# PaxInstruments-T100.net
KiCad netlist of a schematic drawn in EAGLE
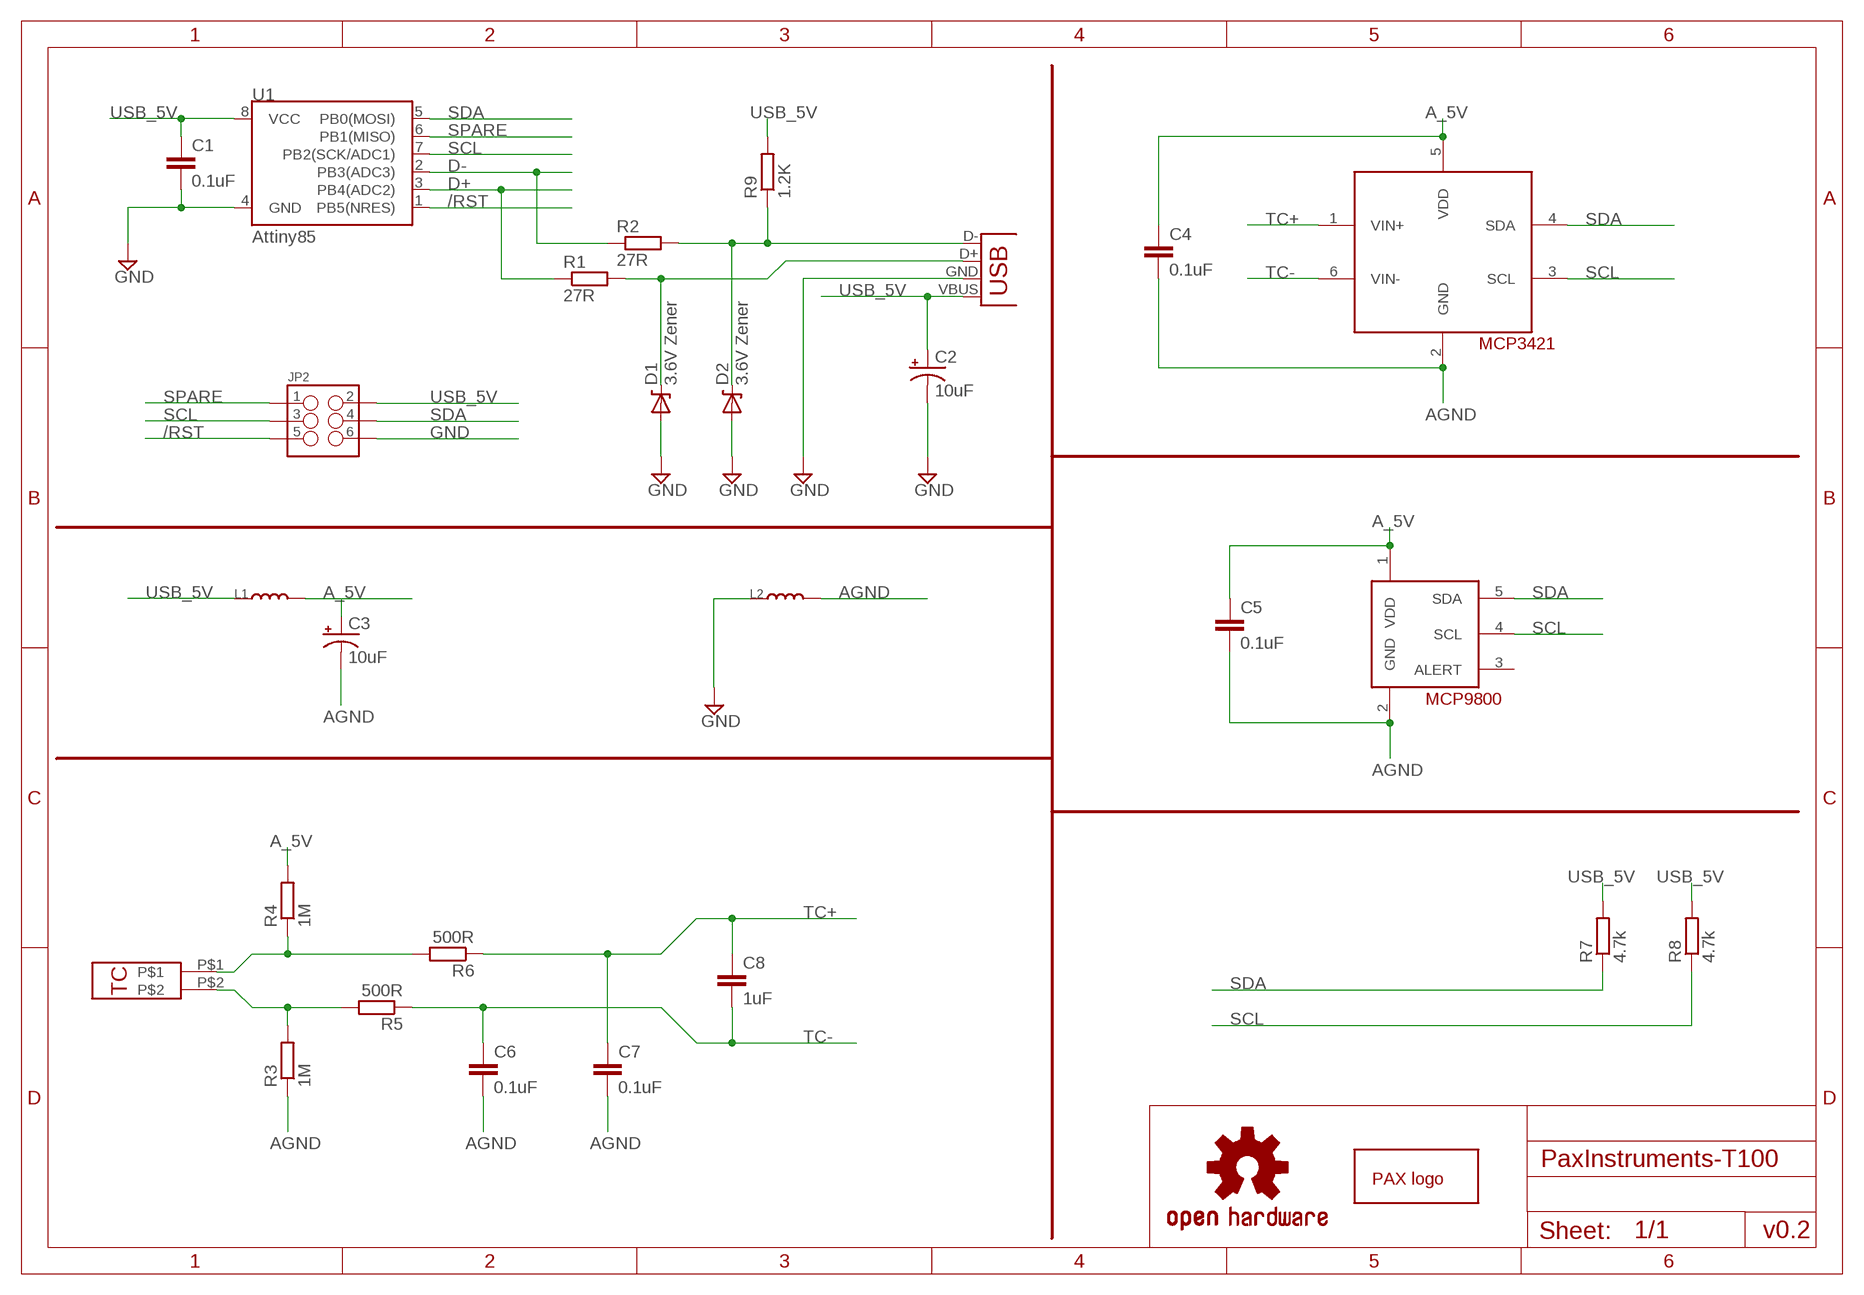
[diagram p0: schematic, sheet 1]

(export (version "E")
  (design (tool "Eeschema 10.0.6"))
  (components
    (comp (ref "C1")
      (value "0.1uF")
      (footprint "eagle-import:C0603")
      (libsource (lib "eagle-import") (part "C-EUC0603"))
    )
    (comp (ref "C2")
      (value "10uF")
      (footprint "eagle-import:EIA3216")
      (libsource (lib "eagle-import") (part "10UF-TANT"))
    )
    (comp (ref "C3")
      (value "10uF")
      (footprint "eagle-import:EIA3216")
      (libsource (lib "eagle-import") (part "10UF-TANT"))
    )
    (comp (ref "C4")
      (value "0.1uF")
      (footprint "eagle-import:C0603")
      (libsource (lib "eagle-import") (part "C-EUC0603"))
    )
    (comp (ref "C5")
      (value "0.1uF")
      (footprint "eagle-import:C0603")
      (libsource (lib "eagle-import") (part "C-EUC0603"))
    )
    (comp (ref "C6")
      (value "0.1uF")
      (footprint "eagle-import:C0603")
      (libsource (lib "eagle-import") (part "C-EUC0603"))
    )
    (comp (ref "C7")
      (value "0.1uF")
      (footprint "eagle-import:C0603")
      (libsource (lib "eagle-import") (part "C-EUC0603"))
    )
    (comp (ref "C8")
      (value "1uF")
      (footprint "eagle-import:C0603")
      (libsource (lib "eagle-import") (part "C-EUC0603"))
    )
    (comp (ref "D1")
      (value "3.6V Zener")
      (footprint "eagle-import:SOD-323")
      (libsource (lib "eagle-import") (part "DIODE-ZENER-BZT52"))
    )
    (comp (ref "D2")
      (value "3.6V Zener")
      (footprint "eagle-import:SOD-323")
      (libsource (lib "eagle-import") (part "DIODE-ZENER-BZT52"))
    )
    (comp (ref "JP1")
      (value "USB-A-H")
      (footprint "eagle-import:USB-A-H")
      (libsource (lib "eagle-import") (part "USB-A-H"))
    )
    (comp (ref "JP2")
      (value "M03X2SMT")
      (footprint "eagle-import:2X3_SMT_POSTS")
      (libsource (lib "eagle-import") (part "M03X2SMT"))
    )
    (comp (ref "L1")
      (value "L-0603")
      (footprint "eagle-import:L0603")
      (libsource (lib "eagle-import") (part "L-0603"))
    )
    (comp (ref "L2")
      (value "L-0603")
      (footprint "eagle-import:L0603")
      (libsource (lib "eagle-import") (part "L-0603"))
    )
    (comp (ref "LOGO1")
      (value "OSHW-LOGOS")
      (footprint "eagle-import:OSHW-LOGO-S")
      (libsource (lib "eagle-import") (part "OSHW-LOGOS"))
    )
    (comp (ref "R1")
      (value "27R")
      (footprint "eagle-import:R0603")
      (libsource (lib "eagle-import") (part "R-EU_R0603"))
    )
    (comp (ref "R2")
      (value "27R")
      (footprint "eagle-import:R0603")
      (libsource (lib "eagle-import") (part "R-EU_R0603"))
    )
    (comp (ref "R3")
      (value "1M")
      (footprint "eagle-import:R0603")
      (libsource (lib "eagle-import") (part "R-EU_R0603"))
    )
    (comp (ref "R4")
      (value "1M")
      (footprint "eagle-import:R0603")
      (libsource (lib "eagle-import") (part "R-EU_R0603"))
    )
    (comp (ref "R5")
      (value "500R")
      (footprint "eagle-import:R0603")
      (libsource (lib "eagle-import") (part "R-EU_R0603"))
    )
    (comp (ref "R6")
      (value "500R")
      (footprint "eagle-import:R0603")
      (libsource (lib "eagle-import") (part "R-EU_R0603"))
    )
    (comp (ref "R7")
      (value "4.7k")
      (footprint "eagle-import:R0603")
      (libsource (lib "eagle-import") (part "R-EU_R0603"))
    )
    (comp (ref "R8")
      (value "4.7k")
      (footprint "eagle-import:R0603")
      (libsource (lib "eagle-import") (part "R-EU_R0603"))
    )
    (comp (ref "R9")
      (value "1.2K")
      (footprint "eagle-import:R0603")
      (libsource (lib "eagle-import") (part "R-EU_R0603"))
    )
    (comp (ref "U$1")
      (value "PAX-LOGO")
      (footprint "eagle-import:PAX-LOGO")
      (libsource (lib "eagle-import") (part "PAX-LOGO"))
    )
    (comp (ref "U$2")
      (value "CHARLESPAX_TC-MINI-CONNECTOR")
      (footprint "eagle-import:CHARLESPAX_TC-MINI-CONNECTOR")
      (libsource (lib "eagle-import") (part "CHARLESPAX_TC-MINI-CONNECTOR"))
    )
    (comp (ref "U$3")
      (value "MCP3421")
      (footprint "eagle-import:SOT23-6")
      (libsource (lib "eagle-import") (part "MCP3421"))
    )
    (comp (ref "U$4")
      (value "MCP9800")
      (footprint "eagle-import:SOT23-5")
      (libsource (lib "eagle-import") (part "MCP9800"))
    )
    (comp (ref "U1")
      (value "Attiny85")
      (footprint "eagle-import:SO08-EIAJ")
      (libsource (lib "eagle-import") (part "ATTINY45TINY45-20-SMT"))
    )
  )
  (nets
    (net (code "1") (name "/AGND") (class "Default")
      (node (ref "C3") (pin "C") (pinfunction "-_C") (pintype "passive"))
      (node (ref "C4") (pin "2") (pinfunction "2_2") (pintype "passive"))
      (node (ref "C5") (pin "2") (pinfunction "2_2") (pintype "passive"))
      (node (ref "C6") (pin "2") (pinfunction "2_2") (pintype "passive"))
      (node (ref "C7") (pin "2") (pinfunction "2_2") (pintype "passive"))
      (node (ref "L2") (pin "2") (pinfunction "2_2") (pintype "passive"))
      (node (ref "R3") (pin "1") (pinfunction "1_1") (pintype "passive"))
      (node (ref "U$3") (pin "2") (pinfunction "GND_2") (pintype "bidirectional"))
      (node (ref "U$4") (pin "2") (pinfunction "GND_2") (pintype "bidirectional"))
    )
    (net (code "2") (name "/A_5V") (class "Default")
      (node (ref "C3") (pin "A") (pinfunction "+_A") (pintype "passive"))
      (node (ref "C4") (pin "1") (pinfunction "1_1") (pintype "passive"))
      (node (ref "C5") (pin "1") (pinfunction "1_1") (pintype "passive"))
      (node (ref "L1") (pin "2") (pinfunction "2_2") (pintype "passive"))
      (node (ref "R4") (pin "2") (pinfunction "2_2") (pintype "passive"))
      (node (ref "U$3") (pin "5") (pinfunction "VDD_5") (pintype "bidirectional"))
      (node (ref "U$4") (pin "1") (pinfunction "VDD_1") (pintype "bidirectional"))
    )
    (net (code "3") (name "/D+") (class "Default")
      (node (ref "R1") (pin "1") (pinfunction "1_1") (pintype "passive"))
      (node (ref "U1") (pin "3") (pinfunction "PB4(ADC2)_3") (pintype "bidirectional"))
    )
    (net (code "4") (name "/D-") (class "Default")
      (node (ref "R2") (pin "1") (pinfunction "1_1") (pintype "passive"))
      (node (ref "U1") (pin "2") (pinfunction "PB3(ADC3)_2") (pintype "bidirectional"))
    )
    (net (code "5") (name "/SCL") (class "Default")
      (node (ref "JP2") (pin "3") (pinfunction "3_3") (pintype "bidirectional"))
      (node (ref "R8") (pin "1") (pinfunction "1_1") (pintype "passive"))
      (node (ref "U$3") (pin "3") (pinfunction "SCL_3") (pintype "bidirectional"))
      (node (ref "U$4") (pin "4") (pinfunction "SCL_4") (pintype "bidirectional"))
      (node (ref "U1") (pin "7") (pinfunction "PB2(SCK/ADC1)_7") (pintype "bidirectional"))
    )
    (net (code "6") (name "/SDA") (class "Default")
      (node (ref "JP2") (pin "4") (pinfunction "4_4") (pintype "bidirectional"))
      (node (ref "R7") (pin "1") (pinfunction "1_1") (pintype "passive"))
      (node (ref "U$3") (pin "4") (pinfunction "SDA_4") (pintype "bidirectional"))
      (node (ref "U$4") (pin "5") (pinfunction "SDA_5") (pintype "bidirectional"))
      (node (ref "U1") (pin "5") (pinfunction "PB0(MOSI)_5") (pintype "bidirectional"))
    )
    (net (code "7") (name "/SPARE") (class "Default")
      (node (ref "JP2") (pin "1") (pinfunction "1_1") (pintype "bidirectional"))
      (node (ref "U1") (pin "6") (pinfunction "PB1(MISO)_6") (pintype "bidirectional"))
    )
    (net (code "8") (name "/TC+") (class "Default")
      (node (ref "C7") (pin "1") (pinfunction "1_1") (pintype "passive"))
      (node (ref "C8") (pin "1") (pinfunction "1_1") (pintype "passive"))
      (node (ref "R6") (pin "1") (pinfunction "1_1") (pintype "passive"))
      (node (ref "U$3") (pin "1") (pinfunction "VIN+_1") (pintype "bidirectional"))
    )
    (net (code "9") (name "/TC-") (class "Default")
      (node (ref "C6") (pin "1") (pinfunction "1_1") (pintype "passive"))
      (node (ref "C8") (pin "2") (pinfunction "2_2") (pintype "passive"))
      (node (ref "R5") (pin "1") (pinfunction "1_1") (pintype "passive"))
      (node (ref "U$3") (pin "6") (pinfunction "VIN-_6") (pintype "bidirectional"))
    )
    (net (code "10") (name "/USB_5V") (class "Default")
      (node (ref "C1") (pin "1") (pinfunction "1_1") (pintype "passive"))
      (node (ref "C2") (pin "A") (pinfunction "+_A") (pintype "passive"))
      (node (ref "JP1") (pin "VBUS") (pinfunction "GND_VBUS") (pintype "bidirectional"))
      (node (ref "JP2") (pin "2") (pinfunction "2_2") (pintype "bidirectional"))
      (node (ref "L1") (pin "1") (pinfunction "1_1") (pintype "passive"))
      (node (ref "R7") (pin "2") (pinfunction "2_2") (pintype "passive"))
      (node (ref "R8") (pin "2") (pinfunction "2_2") (pintype "passive"))
      (node (ref "R9") (pin "2") (pinfunction "2_2") (pintype "passive"))
      (node (ref "U1") (pin "8") (pinfunction "VCC_8") (pintype "bidirectional"))
    )
    (net (code "11") (name "/{slash}RST") (class "Default")
      (node (ref "JP2") (pin "5") (pinfunction "5_5") (pintype "bidirectional"))
      (node (ref "U1") (pin "1") (pinfunction "PB5(NRES)_1") (pintype "bidirectional"))
    )
    (net (code "12") (name "GND") (class "Default")
      (node (ref "C1") (pin "2") (pinfunction "2_2") (pintype "passive"))
      (node (ref "C2") (pin "C") (pinfunction "-_C") (pintype "passive"))
      (node (ref "D1") (pin "2") (pinfunction "A_2") (pintype "passive"))
      (node (ref "D2") (pin "2") (pinfunction "A_2") (pintype "passive"))
      (node (ref "JP1") (pin "GND") (pinfunction "VBUS_GND") (pintype "bidirectional"))
      (node (ref "JP2") (pin "6") (pinfunction "6_6") (pintype "bidirectional"))
      (node (ref "L2") (pin "1") (pinfunction "1_1") (pintype "passive"))
      (node (ref "U1") (pin "4") (pinfunction "GND_4") (pintype "bidirectional"))
    )
    (net (code "13") (name "Net-(D1-C)") (class "Default")
      (node (ref "D1") (pin "1") (pinfunction "C_1") (pintype "passive"))
      (node (ref "JP1") (pin "D+") (pinfunction "D-_D+") (pintype "bidirectional"))
      (node (ref "R1") (pin "2") (pinfunction "2_2") (pintype "passive"))
    )
    (net (code "14") (name "Net-(D2-C)") (class "Default")
      (node (ref "D2") (pin "1") (pinfunction "C_1") (pintype "passive"))
      (node (ref "JP1") (pin "D-") (pinfunction "D+_D-") (pintype "bidirectional"))
      (node (ref "R2") (pin "2") (pinfunction "2_2") (pintype "passive"))
      (node (ref "R9") (pin "1") (pinfunction "1_1") (pintype "passive"))
    )
    (net (code "15") (name "Net-(R3-Pad2)") (class "Default")
      (node (ref "R3") (pin "2") (pinfunction "2_2") (pintype "passive"))
      (node (ref "R5") (pin "2") (pinfunction "2_2") (pintype "passive"))
      (node (ref "U$2") (pin "P$2") (pinfunction "P$2_P$2") (pintype "bidirectional"))
    )
    (net (code "16") (name "Net-(R4-Pad1)") (class "Default")
      (node (ref "R4") (pin "1") (pinfunction "1_1") (pintype "passive"))
      (node (ref "R6") (pin "2") (pinfunction "2_2") (pintype "passive"))
      (node (ref "U$2") (pin "P$1") (pinfunction "P$1_P$1") (pintype "bidirectional"))
    )
    (net (code "17") (name "unconnected-(U$4-ALERT-Pad3)") (class "Default")
      (node (ref "U$4") (pin "3") (pinfunction "ALERT_3") (pintype "bidirectional"))
    )
  )
)
